# Circuito.net
KiCad netlist of a schematic drawn in EAGLE
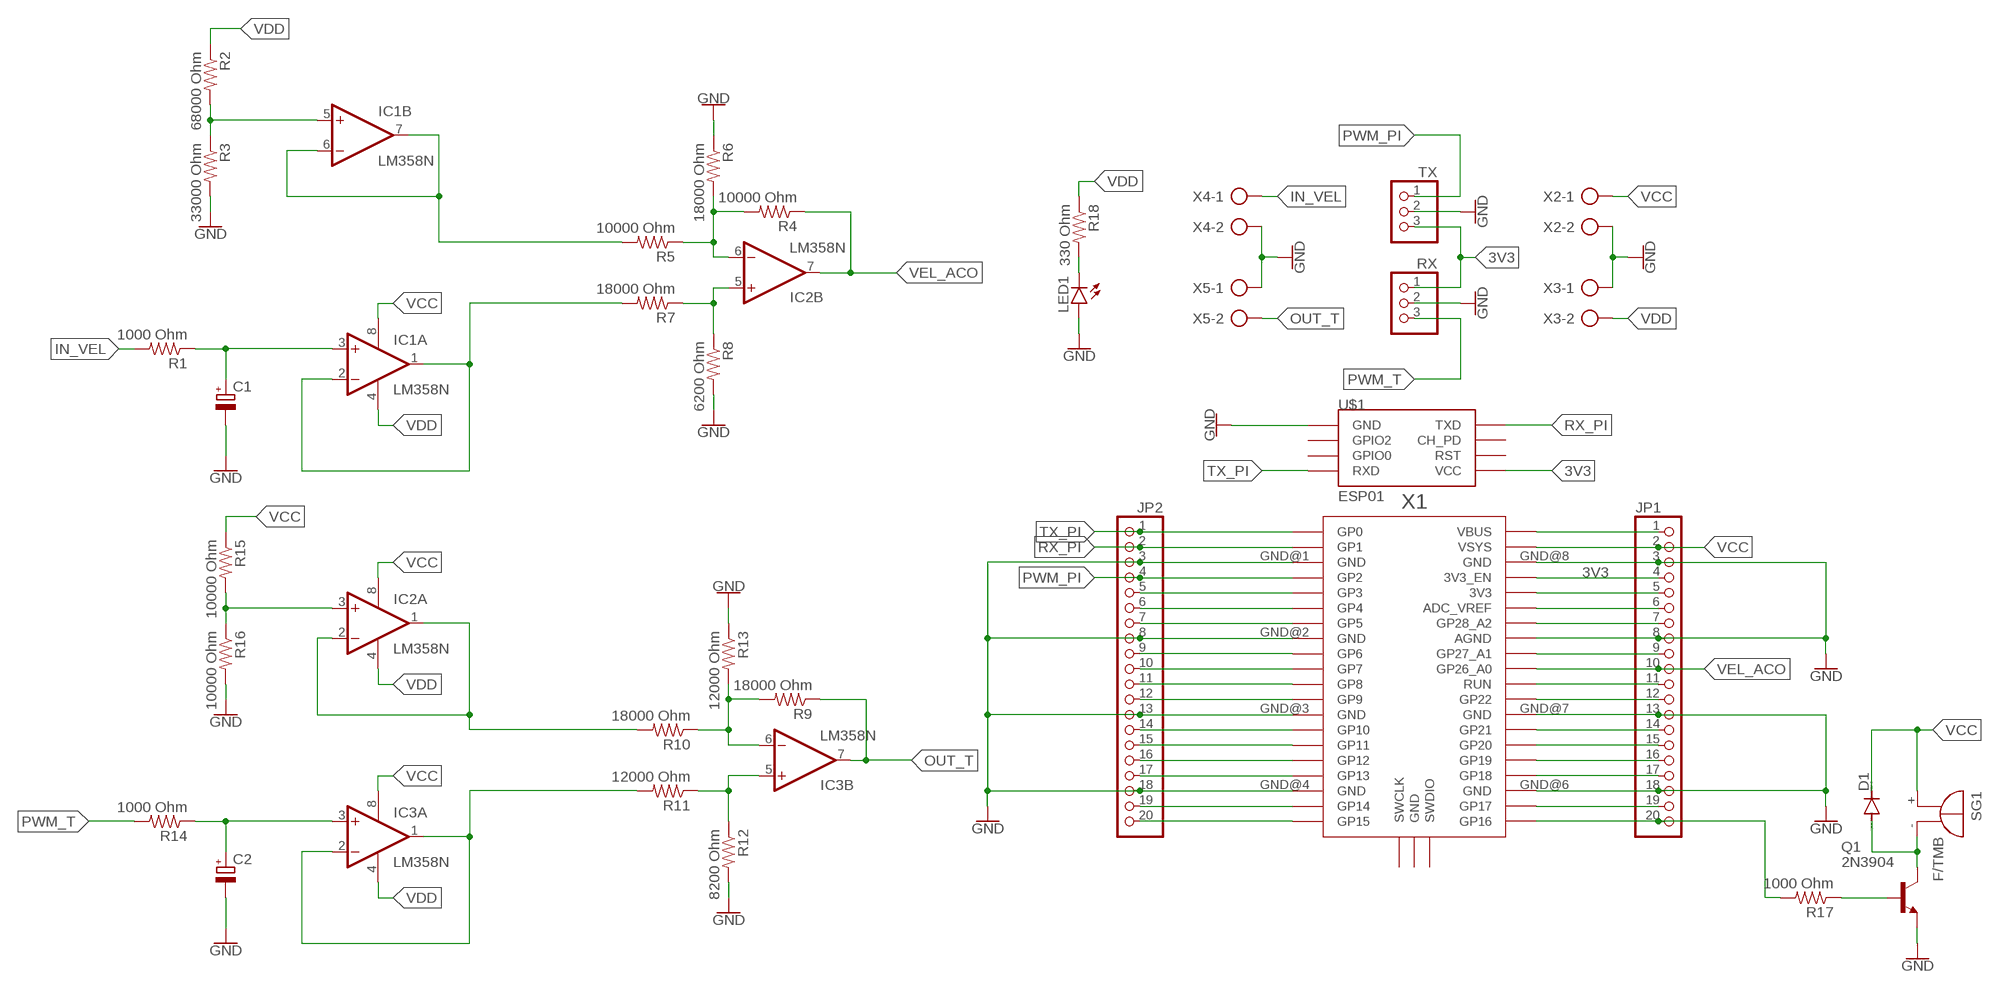
[diagram p0: schematic, sheet 1]

(export (version "E")
  (design (tool "Eeschema 10.0.6"))
  (components
    (comp (ref "C1")
      (value "CPOL-EUE2.5-6")
      (footprint "eagle-import:E2,5-6")
      (libsource (lib "eagle-import") (part "CPOL-EUE2.5-6"))
    )
    (comp (ref "C2")
      (value "CPOL-EUE2.5-6")
      (footprint "eagle-import:E2,5-6")
      (libsource (lib "eagle-import") (part "CPOL-EUE2.5-6"))
    )
    (comp (ref "D1")
      (value "DIODE-DO15-12")
      (footprint "eagle-import:DO15-12")
      (libsource (lib "eagle-import") (part "DIODE-DO15-12"))
    )
    (comp (ref "IC1")
      (value "LM358N")
      (footprint "eagle-import:DIL08")
      (libsource (lib "eagle-import") (part "LM358N"))
    )
    (comp (ref "IC2")
      (value "LM358N")
      (footprint "eagle-import:DIL08")
      (libsource (lib "eagle-import") (part "LM358N"))
    )
    (comp (ref "IC3")
      (value "LM358N")
      (footprint "eagle-import:DIL08")
      (libsource (lib "eagle-import") (part "LM358N"))
    )
    (comp (ref "JP1")
      (value "PINHD-1X20")
      (footprint "eagle-import:1X20")
      (libsource (lib "eagle-import") (part "PINHD-1X20"))
    )
    (comp (ref "JP2")
      (value "PINHD-1X20")
      (footprint "eagle-import:1X20")
      (libsource (lib "eagle-import") (part "PINHD-1X20"))
    )
    (comp (ref "LED1")
      (value "LED3MM")
      (footprint "eagle-import:LED3MM")
      (libsource (lib "eagle-import") (part "LED3MM"))
    )
    (comp (ref "Q1")
      (value "2N3904")
      (footprint "eagle-import:TO92")
      (libsource (lib "eagle-import") (part "2N3904"))
    )
    (comp (ref "R1")
      (value "1000 Ohm")
      (footprint "eagle-import:0207_10")
      (libsource (lib "eagle-import") (part "R-US_0207/10"))
    )
    (comp (ref "R2")
      (value "68000 Ohm")
      (footprint "eagle-import:0207_10")
      (libsource (lib "eagle-import") (part "R-US_0207/10"))
    )
    (comp (ref "R3")
      (value "33000 Ohm")
      (footprint "eagle-import:0207_10")
      (libsource (lib "eagle-import") (part "R-US_0207/10"))
    )
    (comp (ref "R4")
      (value "10000 Ohm")
      (footprint "eagle-import:0207_10")
      (libsource (lib "eagle-import") (part "R-US_0207/10"))
    )
    (comp (ref "R5")
      (value "10000 Ohm")
      (footprint "eagle-import:0207_10")
      (libsource (lib "eagle-import") (part "R-US_0207/10"))
    )
    (comp (ref "R6")
      (value "18000 Ohm")
      (footprint "eagle-import:0207_10")
      (libsource (lib "eagle-import") (part "R-US_0207/10"))
    )
    (comp (ref "R7")
      (value "18000 Ohm")
      (footprint "eagle-import:0207_10")
      (libsource (lib "eagle-import") (part "R-US_0207/10"))
    )
    (comp (ref "R8")
      (value "6200 Ohm")
      (footprint "eagle-import:0207_10")
      (libsource (lib "eagle-import") (part "R-US_0207/10"))
    )
    (comp (ref "R9")
      (value "18000 Ohm")
      (footprint "eagle-import:0207_10")
      (libsource (lib "eagle-import") (part "R-US_0207/10"))
    )
    (comp (ref "R10")
      (value "18000 Ohm")
      (footprint "eagle-import:0207_10")
      (libsource (lib "eagle-import") (part "R-US_0207/10"))
    )
    (comp (ref "R11")
      (value "12000 Ohm")
      (footprint "eagle-import:0207_10")
      (libsource (lib "eagle-import") (part "R-US_0207/10"))
    )
    (comp (ref "R12")
      (value "8200 Ohm")
      (footprint "eagle-import:0207_10")
      (libsource (lib "eagle-import") (part "R-US_0207/10"))
    )
    (comp (ref "R13")
      (value "12000 Ohm")
      (footprint "eagle-import:0207_10")
      (libsource (lib "eagle-import") (part "R-US_0207/10"))
    )
    (comp (ref "R14")
      (value "1000 Ohm")
      (footprint "eagle-import:0207_10")
      (libsource (lib "eagle-import") (part "R-US_0207/10"))
    )
    (comp (ref "R15")
      (value "10000 Ohm")
      (footprint "eagle-import:0207_10")
      (libsource (lib "eagle-import") (part "R-US_0207/10"))
    )
    (comp (ref "R16")
      (value "10000 Ohm")
      (footprint "eagle-import:0207_10")
      (libsource (lib "eagle-import") (part "R-US_0207/10"))
    )
    (comp (ref "R17")
      (value "1000 Ohm")
      (footprint "eagle-import:0207_10")
      (libsource (lib "eagle-import") (part "R-US_0207/10"))
    )
    (comp (ref "R18")
      (value "330 Ohm")
      (footprint "eagle-import:0207_10")
      (libsource (lib "eagle-import") (part "R-US_0207/10"))
    )
    (comp (ref "RX")
      (value "PINHD-1X3")
      (footprint "eagle-import:1X03")
      (libsource (lib "eagle-import") (part "PINHD-1X3"))
    )
    (comp (ref "SG1")
      (value "F/TMB")
      (footprint "eagle-import:F_TMB")
      (libsource (lib "eagle-import") (part "F/TMB"))
    )
    (comp (ref "TX")
      (value "PINHD-1X3")
      (footprint "eagle-import:1X03")
      (libsource (lib "eagle-import") (part "PINHD-1X3"))
    )
    (comp (ref "U$1")
      (value "ESP01")
      (footprint "eagle-import:ESP01")
      (libsource (lib "eagle-import") (part "ESP01"))
    )
    (comp (ref "X1")
      (value "RPI_PICO_IG-TH")
      (footprint "eagle-import:RPI_PICO_TH")
      (libsource (lib "eagle-import") (part "RPI_PICO_IG-TH"))
    )
    (comp (ref "X2")
      (value "AK500/2")
      (footprint "eagle-import:AK500_2")
      (libsource (lib "eagle-import") (part "AK500/2"))
    )
    (comp (ref "X3")
      (value "AK500/2")
      (footprint "eagle-import:AK500_2")
      (libsource (lib "eagle-import") (part "AK500/2"))
    )
    (comp (ref "X4")
      (value "AK500/2")
      (footprint "eagle-import:AK500_2")
      (libsource (lib "eagle-import") (part "AK500/2"))
    )
    (comp (ref "X5")
      (value "AK500/2")
      (footprint "eagle-import:AK500_2")
      (libsource (lib "eagle-import") (part "AK500/2"))
    )
  )
  (nets
    (net (code "1") (name "3V3") (class "Default")
      (node (ref "JP1") (pin "4") (pinfunction "4_4") (pintype "passive"))
      (node (ref "RX") (pin "1") (pinfunction "1_1") (pintype "passive"))
      (node (ref "TX") (pin "3") (pinfunction "3_3") (pintype "passive"))
      (node (ref "U$1") (pin "VCC") (pinfunction "VCC_VCC") (pintype "bidirectional"))
      (node (ref "X1") (pin "3V3_EN") (pinfunction "3V3_EN_3V3_EN") (pintype "bidirectional"))
    )
    (net (code "2") (name "GND") (class "Default")
      (node (ref "C1") (pin "-") (pinfunction "-_-") (pintype "passive"))
      (node (ref "C2") (pin "-") (pinfunction "-_-") (pintype "passive"))
      (node (ref "JP1") (pin "13") (pinfunction "13_13") (pintype "passive"))
      (node (ref "JP1") (pin "18") (pinfunction "18_18") (pintype "passive"))
      (node (ref "JP1") (pin "3") (pinfunction "3_3") (pintype "passive"))
      (node (ref "JP1") (pin "8") (pinfunction "8_8") (pintype "passive"))
      (node (ref "JP2") (pin "13") (pinfunction "13_13") (pintype "passive"))
      (node (ref "JP2") (pin "18") (pinfunction "18_18") (pintype "passive"))
      (node (ref "JP2") (pin "3") (pinfunction "3_3") (pintype "passive"))
      (node (ref "JP2") (pin "8") (pinfunction "8_8") (pintype "passive"))
      (node (ref "LED1") (pin "A") (pinfunction "A_A") (pintype "passive"))
      (node (ref "Q1") (pin "3") (pinfunction "E_3") (pintype "passive"))
      (node (ref "R12") (pin "2") (pinfunction "2_2") (pintype "passive"))
      (node (ref "R13") (pin "1") (pinfunction "1_1") (pintype "passive"))
      (node (ref "R16") (pin "2") (pinfunction "2_2") (pintype "passive"))
      (node (ref "R3") (pin "2") (pinfunction "2_2") (pintype "passive"))
      (node (ref "R6") (pin "1") (pinfunction "1_1") (pintype "passive"))
      (node (ref "R8") (pin "2") (pinfunction "2_2") (pintype "passive"))
      (node (ref "RX") (pin "2") (pinfunction "2_2") (pintype "passive"))
      (node (ref "TX") (pin "2") (pinfunction "2_2") (pintype "passive"))
      (node (ref "U$1") (pin "GND") (pinfunction "GND_GND") (pintype "bidirectional"))
      (node (ref "X1") (pin "AGND") (pinfunction "AGND_AGND") (pintype "bidirectional"))
      (node (ref "X1") (pin "GND@1") (pinfunction "GND_GND@1") (pintype "bidirectional"))
      (node (ref "X1") (pin "GND@2") (pinfunction "GND_GND@2") (pintype "bidirectional"))
      (node (ref "X1") (pin "GND@3") (pinfunction "GND_GND@3") (pintype "bidirectional"))
      (node (ref "X1") (pin "GND@4") (pinfunction "GND_GND@4") (pintype "bidirectional"))
      (node (ref "X1") (pin "GND@6") (pinfunction "GND_GND@6") (pintype "bidirectional"))
      (node (ref "X1") (pin "GND@7") (pinfunction "GND_GND@7") (pintype "bidirectional"))
      (node (ref "X1") (pin "GND@8") (pinfunction "GND_GND@8") (pintype "bidirectional"))
      (node (ref "X2") (pin "2") (pinfunction "KL_2") (pintype "passive"))
      (node (ref "X3") (pin "1") (pinfunction "KL_1") (pintype "passive"))
      (node (ref "X4") (pin "2") (pinfunction "KL_2") (pintype "passive"))
      (node (ref "X5") (pin "1") (pinfunction "KL_1") (pintype "passive"))
    )
    (net (code "3") (name "IN_VEL") (class "Default")
      (node (ref "R1") (pin "2") (pinfunction "2_2") (pintype "passive"))
      (node (ref "X4") (pin "1") (pinfunction "KL_1") (pintype "passive"))
    )
    (net (code "4") (name "Net-(IC1A-+IN)") (class "Default")
      (node (ref "C1") (pin "+") (pinfunction "+_+") (pintype "passive"))
      (node (ref "IC1") (pin "3") (pinfunction "+IN_3") (pintype "input"))
      (node (ref "R1") (pin "1") (pinfunction "1_1") (pintype "passive"))
    )
    (net (code "5") (name "Net-(IC1A--IN)") (class "Default")
      (node (ref "IC1") (pin "1") (pinfunction "OUT_1") (pintype "output"))
      (node (ref "IC1") (pin "2") (pinfunction "-IN_2") (pintype "input"))
      (node (ref "R7") (pin "2") (pinfunction "2_2") (pintype "passive"))
    )
    (net (code "6") (name "Net-(IC1B-+IN)") (class "Default")
      (node (ref "IC1") (pin "5") (pinfunction "+IN_5") (pintype "input"))
      (node (ref "R2") (pin "2") (pinfunction "2_2") (pintype "passive"))
      (node (ref "R3") (pin "1") (pinfunction "1_1") (pintype "passive"))
    )
    (net (code "7") (name "Net-(IC1B--IN)") (class "Default")
      (node (ref "IC1") (pin "6") (pinfunction "-IN_6") (pintype "input"))
      (node (ref "IC1") (pin "7") (pinfunction "OUT_7") (pintype "output"))
      (node (ref "R5") (pin "2") (pinfunction "2_2") (pintype "passive"))
    )
    (net (code "8") (name "Net-(IC2A-+IN)") (class "Default")
      (node (ref "IC2") (pin "3") (pinfunction "+IN_3") (pintype "input"))
      (node (ref "R15") (pin "2") (pinfunction "2_2") (pintype "passive"))
      (node (ref "R16") (pin "1") (pinfunction "1_1") (pintype "passive"))
    )
    (net (code "9") (name "Net-(IC2A--IN)") (class "Default")
      (node (ref "IC2") (pin "1") (pinfunction "OUT_1") (pintype "output"))
      (node (ref "IC2") (pin "2") (pinfunction "-IN_2") (pintype "input"))
      (node (ref "R10") (pin "2") (pinfunction "2_2") (pintype "passive"))
    )
    (net (code "10") (name "Net-(IC2B-+IN)") (class "Default")
      (node (ref "IC2") (pin "5") (pinfunction "+IN_5") (pintype "input"))
      (node (ref "R7") (pin "1") (pinfunction "1_1") (pintype "passive"))
      (node (ref "R8") (pin "1") (pinfunction "1_1") (pintype "passive"))
    )
    (net (code "11") (name "Net-(IC2B--IN)") (class "Default")
      (node (ref "IC2") (pin "6") (pinfunction "-IN_6") (pintype "input"))
      (node (ref "R4") (pin "2") (pinfunction "2_2") (pintype "passive"))
      (node (ref "R5") (pin "1") (pinfunction "1_1") (pintype "passive"))
      (node (ref "R6") (pin "2") (pinfunction "2_2") (pintype "passive"))
    )
    (net (code "12") (name "Net-(IC3A-+IN)") (class "Default")
      (node (ref "C2") (pin "+") (pinfunction "+_+") (pintype "passive"))
      (node (ref "IC3") (pin "3") (pinfunction "+IN_3") (pintype "input"))
      (node (ref "R14") (pin "1") (pinfunction "1_1") (pintype "passive"))
    )
    (net (code "13") (name "Net-(IC3A--IN)") (class "Default")
      (node (ref "IC3") (pin "1") (pinfunction "OUT_1") (pintype "output"))
      (node (ref "IC3") (pin "2") (pinfunction "-IN_2") (pintype "input"))
      (node (ref "R11") (pin "2") (pinfunction "2_2") (pintype "passive"))
    )
    (net (code "14") (name "Net-(IC3B-+IN)") (class "Default")
      (node (ref "IC3") (pin "5") (pinfunction "+IN_5") (pintype "input"))
      (node (ref "R11") (pin "1") (pinfunction "1_1") (pintype "passive"))
      (node (ref "R12") (pin "1") (pinfunction "1_1") (pintype "passive"))
    )
    (net (code "15") (name "Net-(IC3B--IN)") (class "Default")
      (node (ref "IC3") (pin "6") (pinfunction "-IN_6") (pintype "input"))
      (node (ref "R10") (pin "1") (pinfunction "1_1") (pintype "passive"))
      (node (ref "R13") (pin "2") (pinfunction "2_2") (pintype "passive"))
      (node (ref "R9") (pin "2") (pinfunction "2_2") (pintype "passive"))
    )
    (net (code "16") (name "Net-(JP1-Pad1)") (class "Default")
      (node (ref "JP1") (pin "1") (pinfunction "1_1") (pintype "passive"))
      (node (ref "X1") (pin "VBUS") (pinfunction "VBUS_VBUS") (pintype "bidirectional"))
    )
    (net (code "17") (name "Net-(JP1-Pad5)") (class "Default")
      (node (ref "JP1") (pin "5") (pinfunction "5_5") (pintype "passive"))
      (node (ref "X1") (pin "3V3") (pinfunction "3V3_3V3") (pintype "bidirectional"))
    )
    (net (code "18") (name "Net-(JP1-Pad6)") (class "Default")
      (node (ref "JP1") (pin "6") (pinfunction "6_6") (pintype "passive"))
      (node (ref "X1") (pin "ADC_VREF") (pinfunction "ADC_VREF_ADC_VREF") (pintype "bidirectional"))
    )
    (net (code "19") (name "Net-(JP1-Pad7)") (class "Default")
      (node (ref "JP1") (pin "7") (pinfunction "7_7") (pintype "passive"))
      (node (ref "X1") (pin "GP28_A2") (pinfunction "GP28_A2_GP28_A2") (pintype "bidirectional"))
    )
    (net (code "20") (name "Net-(JP1-Pad9)") (class "Default")
      (node (ref "JP1") (pin "9") (pinfunction "9_9") (pintype "passive"))
      (node (ref "X1") (pin "GP27_A1") (pinfunction "GP27_A1_GP27_A1") (pintype "bidirectional"))
    )
    (net (code "21") (name "Net-(JP1-Pad11)") (class "Default")
      (node (ref "JP1") (pin "11") (pinfunction "11_11") (pintype "passive"))
      (node (ref "X1") (pin "RUN") (pinfunction "RUN_RUN") (pintype "bidirectional"))
    )
    (net (code "22") (name "Net-(JP1-Pad12)") (class "Default")
      (node (ref "JP1") (pin "12") (pinfunction "12_12") (pintype "passive"))
      (node (ref "X1") (pin "GP22") (pinfunction "GP22_GP22") (pintype "bidirectional"))
    )
    (net (code "23") (name "Net-(JP1-Pad14)") (class "Default")
      (node (ref "JP1") (pin "14") (pinfunction "14_14") (pintype "passive"))
      (node (ref "X1") (pin "GP21") (pinfunction "GP21_GP21") (pintype "bidirectional"))
    )
    (net (code "24") (name "Net-(JP1-Pad15)") (class "Default")
      (node (ref "JP1") (pin "15") (pinfunction "15_15") (pintype "passive"))
      (node (ref "X1") (pin "GP20") (pinfunction "GP20_GP20") (pintype "bidirectional"))
    )
    (net (code "25") (name "Net-(JP1-Pad16)") (class "Default")
      (node (ref "JP1") (pin "16") (pinfunction "16_16") (pintype "passive"))
      (node (ref "X1") (pin "GP19") (pinfunction "GP19_GP19") (pintype "bidirectional"))
    )
    (net (code "26") (name "Net-(JP1-Pad17)") (class "Default")
      (node (ref "JP1") (pin "17") (pinfunction "17_17") (pintype "passive"))
      (node (ref "X1") (pin "GP18") (pinfunction "GP18_GP18") (pintype "bidirectional"))
    )
    (net (code "27") (name "Net-(JP1-Pad19)") (class "Default")
      (node (ref "JP1") (pin "19") (pinfunction "19_19") (pintype "passive"))
      (node (ref "X1") (pin "GP17") (pinfunction "GP17_GP17") (pintype "bidirectional"))
    )
    (net (code "28") (name "Net-(JP1-Pad20)") (class "Default")
      (node (ref "JP1") (pin "20") (pinfunction "20_20") (pintype "passive"))
      (node (ref "R17") (pin "2") (pinfunction "2_2") (pintype "passive"))
      (node (ref "X1") (pin "GP16") (pinfunction "GP16_GP16") (pintype "bidirectional"))
    )
    (net (code "29") (name "Net-(JP2-Pad5)") (class "Default")
      (node (ref "JP2") (pin "5") (pinfunction "5_5") (pintype "passive"))
      (node (ref "X1") (pin "GP3") (pinfunction "GP3_GP3") (pintype "bidirectional"))
    )
    (net (code "30") (name "Net-(JP2-Pad6)") (class "Default")
      (node (ref "JP2") (pin "6") (pinfunction "6_6") (pintype "passive"))
      (node (ref "X1") (pin "GP4") (pinfunction "GP4_GP4") (pintype "bidirectional"))
    )
    (net (code "31") (name "Net-(JP2-Pad7)") (class "Default")
      (node (ref "JP2") (pin "7") (pinfunction "7_7") (pintype "passive"))
      (node (ref "X1") (pin "GP5") (pinfunction "GP5_GP5") (pintype "bidirectional"))
    )
    (net (code "32") (name "Net-(JP2-Pad9)") (class "Default")
      (node (ref "JP2") (pin "9") (pinfunction "9_9") (pintype "passive"))
      (node (ref "X1") (pin "GP6") (pinfunction "GP6_GP6") (pintype "bidirectional"))
    )
    (net (code "33") (name "Net-(JP2-Pad10)") (class "Default")
      (node (ref "JP2") (pin "10") (pinfunction "10_10") (pintype "passive"))
      (node (ref "X1") (pin "GP7") (pinfunction "GP7_GP7") (pintype "bidirectional"))
    )
    (net (code "34") (name "Net-(JP2-Pad11)") (class "Default")
      (node (ref "JP2") (pin "11") (pinfunction "11_11") (pintype "passive"))
      (node (ref "X1") (pin "GP8") (pinfunction "GP8_GP8") (pintype "bidirectional"))
    )
    (net (code "35") (name "Net-(JP2-Pad12)") (class "Default")
      (node (ref "JP2") (pin "12") (pinfunction "12_12") (pintype "passive"))
      (node (ref "X1") (pin "GP9") (pinfunction "GP9_GP9") (pintype "bidirectional"))
    )
    (net (code "36") (name "Net-(JP2-Pad14)") (class "Default")
      (node (ref "JP2") (pin "14") (pinfunction "14_14") (pintype "passive"))
      (node (ref "X1") (pin "GP10") (pinfunction "GP10_GP10") (pintype "bidirectional"))
    )
    (net (code "37") (name "Net-(JP2-Pad15)") (class "Default")
      (node (ref "JP2") (pin "15") (pinfunction "15_15") (pintype "passive"))
      (node (ref "X1") (pin "GP11") (pinfunction "GP11_GP11") (pintype "bidirectional"))
    )
    (net (code "38") (name "Net-(JP2-Pad16)") (class "Default")
      (node (ref "JP2") (pin "16") (pinfunction "16_16") (pintype "passive"))
      (node (ref "X1") (pin "GP12") (pinfunction "GP12_GP12") (pintype "bidirectional"))
    )
    (net (code "39") (name "Net-(JP2-Pad17)") (class "Default")
      (node (ref "JP2") (pin "17") (pinfunction "17_17") (pintype "passive"))
      (node (ref "X1") (pin "GP13") (pinfunction "GP13_GP13") (pintype "bidirectional"))
    )
    (net (code "40") (name "Net-(JP2-Pad19)") (class "Default")
      (node (ref "JP2") (pin "19") (pinfunction "19_19") (pintype "passive"))
      (node (ref "X1") (pin "GP14") (pinfunction "GP14_GP14") (pintype "bidirectional"))
    )
    (net (code "41") (name "Net-(JP2-Pad20)") (class "Default")
      (node (ref "JP2") (pin "20") (pinfunction "20_20") (pintype "passive"))
      (node (ref "X1") (pin "GP15") (pinfunction "GP15_GP15") (pintype "bidirectional"))
    )
    (net (code "42") (name "Net-(LED1-C)") (class "Default")
      (node (ref "LED1") (pin "K") (pinfunction "C_K") (pintype "passive"))
      (node (ref "R18") (pin "2") (pinfunction "2_2") (pintype "passive"))
    )
    (net (code "43") (name "Net-(Q1-B)") (class "Default")
      (node (ref "Q1") (pin "2") (pinfunction "B_2") (pintype "passive"))
      (node (ref "R17") (pin "1") (pinfunction "1_1") (pintype "passive"))
    )
    (net (code "44") (name "Net-(Q1-C)") (class "Default")
      (node (ref "D1") (pin "A") (pinfunction "A_A") (pintype "passive"))
      (node (ref "Q1") (pin "1") (pinfunction "C_1") (pintype "passive"))
      (node (ref "SG1") (pin "-") (pinfunction "-_-") (pintype "passive"))
    )
    (net (code "45") (name "OUT_T") (class "Default")
      (node (ref "IC3") (pin "7") (pinfunction "OUT_7") (pintype "output"))
      (node (ref "R9") (pin "1") (pinfunction "1_1") (pintype "passive"))
      (node (ref "X5") (pin "2") (pinfunction "KL_2") (pintype "passive"))
    )
    (net (code "46") (name "PWM_PI") (class "Default")
      (node (ref "JP2") (pin "4") (pinfunction "4_4") (pintype "passive"))
      (node (ref "TX") (pin "1") (pinfunction "1_1") (pintype "passive"))
      (node (ref "X1") (pin "GP2") (pinfunction "GP2_GP2") (pintype "bidirectional"))
    )
    (net (code "47") (name "PWM_T") (class "Default")
      (node (ref "R14") (pin "2") (pinfunction "2_2") (pintype "passive"))
      (node (ref "RX") (pin "3") (pinfunction "3_3") (pintype "passive"))
    )
    (net (code "48") (name "RX_PI") (class "Default")
      (node (ref "JP2") (pin "2") (pinfunction "2_2") (pintype "passive"))
      (node (ref "U$1") (pin "TX") (pinfunction "TXD_TX") (pintype "bidirectional"))
      (node (ref "X1") (pin "GP1") (pinfunction "GP1_GP1") (pintype "bidirectional"))
    )
    (net (code "49") (name "TX_PI") (class "Default")
      (node (ref "JP2") (pin "1") (pinfunction "1_1") (pintype "passive"))
      (node (ref "U$1") (pin "RX") (pinfunction "RXD_RX") (pintype "bidirectional"))
      (node (ref "X1") (pin "GP0") (pinfunction "GP0_GP0") (pintype "bidirectional"))
    )
    (net (code "50") (name "VCC") (class "Default")
      (node (ref "D1") (pin "C") (pinfunction "C_C") (pintype "passive"))
      (node (ref "IC1") (pin "8") (pinfunction "V+_8") (pintype "power_in"))
      (node (ref "IC2") (pin "8") (pinfunction "V+_8") (pintype "power_in"))
      (node (ref "IC3") (pin "8") (pinfunction "V+_8") (pintype "power_in"))
      (node (ref "JP1") (pin "2") (pinfunction "2_2") (pintype "passive"))
      (node (ref "R15") (pin "1") (pinfunction "1_1") (pintype "passive"))
      (node (ref "SG1") (pin "+") (pinfunction "+_+") (pintype "passive"))
      (node (ref "X1") (pin "VSYS") (pinfunction "VSYS_VSYS") (pintype "bidirectional"))
      (node (ref "X2") (pin "1") (pinfunction "KL_1") (pintype "passive"))
    )
    (net (code "51") (name "VDD") (class "Default")
      (node (ref "IC1") (pin "4") (pinfunction "V-_4") (pintype "power_in"))
      (node (ref "IC2") (pin "4") (pinfunction "V-_4") (pintype "power_in"))
      (node (ref "IC3") (pin "4") (pinfunction "V-_4") (pintype "power_in"))
      (node (ref "R18") (pin "1") (pinfunction "1_1") (pintype "passive"))
      (node (ref "R2") (pin "1") (pinfunction "1_1") (pintype "passive"))
      (node (ref "X3") (pin "2") (pinfunction "KL_2") (pintype "passive"))
    )
    (net (code "52") (name "VEL_ACO") (class "Default")
      (node (ref "IC2") (pin "7") (pinfunction "OUT_7") (pintype "output"))
      (node (ref "JP1") (pin "10") (pinfunction "10_10") (pintype "passive"))
      (node (ref "R4") (pin "1") (pinfunction "1_1") (pintype "passive"))
      (node (ref "X1") (pin "GP26_A0") (pinfunction "GP26_A0_GP26_A0") (pintype "bidirectional"))
    )
    (net (code "53") (name "unconnected-(U$1-PadCH_PD)") (class "Default")
      (node (ref "U$1") (pin "CH_PD") (pinfunction "CH_PD_CH_PD") (pintype "bidirectional"))
    )
    (net (code "54") (name "unconnected-(U$1-PadGPIO0)") (class "Default")
      (node (ref "U$1") (pin "GPIO0") (pinfunction "GPIO0_GPIO0") (pintype "bidirectional"))
    )
    (net (code "55") (name "unconnected-(U$1-PadGPIO2)") (class "Default")
      (node (ref "U$1") (pin "GPIO2") (pinfunction "GPIO2_GPIO2") (pintype "bidirectional"))
    )
    (net (code "56") (name "unconnected-(U$1-PadRST)") (class "Default")
      (node (ref "U$1") (pin "RST") (pinfunction "RST_RST") (pintype "bidirectional"))
    )
    (net (code "57") (name "unconnected-(X1-GND-PadGND@5)") (class "Default")
      (node (ref "X1") (pin "GND@5") (pinfunction "GND_GND@5") (pintype "bidirectional"))
    )
    (net (code "58") (name "unconnected-(X1-PadSWCLK)") (class "Default")
      (node (ref "X1") (pin "SWCLK") (pinfunction "SWCLK_SWCLK") (pintype "bidirectional"))
    )
    (net (code "59") (name "unconnected-(X1-PadSWDIO)") (class "Default")
      (node (ref "X1") (pin "SWDIO") (pinfunction "SWDIO_SWDIO") (pintype "bidirectional"))
    )
  )
)
